# firefly.net
KiCad netlist of a schematic drawn in EAGLE
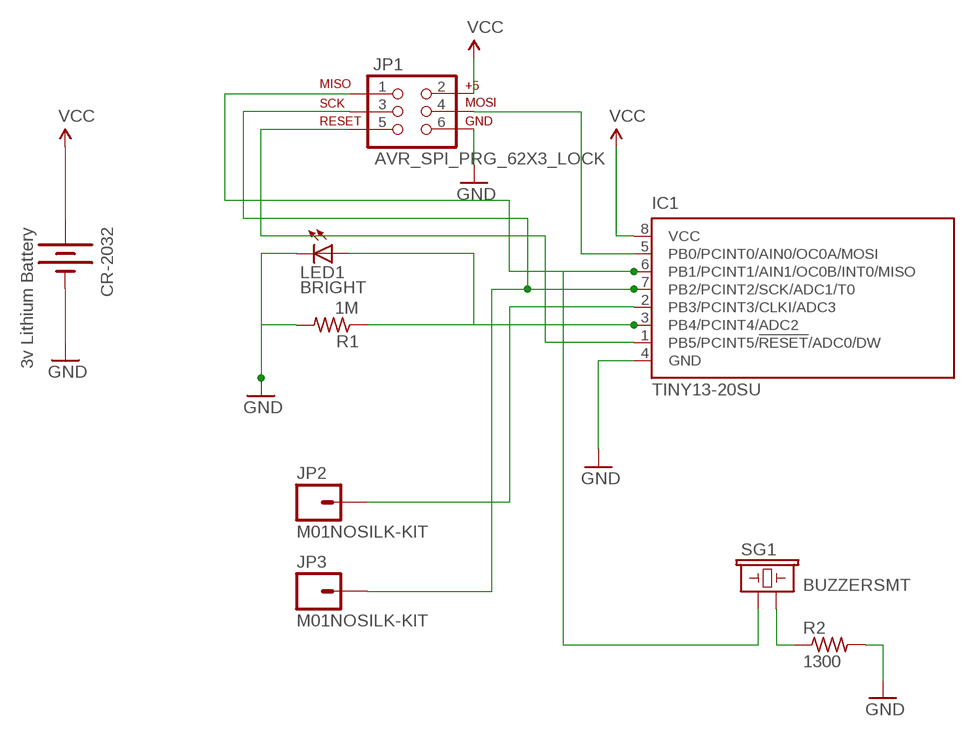
[diagram p0: schematic, sheet 1]

(export (version "E")
  (design (tool "Eeschema 10.0.6"))
  (components
    (comp (ref "CR-2032")
      (value "3v Lithium Battery")
      (footprint "eagle-import:BATTCON_20MM_4LEGS")
      (libsource (lib "eagle-import") (part "BATTERY20MM_4LEGS"))
    )
    (comp (ref "IC1")
      (value "TINY13-20SU")
      (footprint "eagle-import:8S2")
      (fields (field (name "MPN") "ATTINY13-20SU"))
      (libsource (lib "eagle-import") (part "TINY13SU-20"))
    )
    (comp (ref "JP1")
      (value "AVR_SPI_PRG_62X3_LOCK")
      (footprint "eagle-import:2X3_LOCK")
      (libsource (lib "eagle-import") (part "AVR_SPI_PRG_62X3_LOCK"))
    )
    (comp (ref "JP2")
      (value "M01NOSILK-KIT")
      (footprint "eagle-import:1X01NS-KIT")
      (libsource (lib "eagle-import") (part "M01NOSILK-KIT"))
    )
    (comp (ref "JP3")
      (value "M01NOSILK-KIT")
      (footprint "eagle-import:1X01NS-KIT")
      (libsource (lib "eagle-import") (part "M01NOSILK-KIT"))
    )
    (comp (ref "LED1")
      (value "BRIGHT")
      (footprint "eagle-import:CHIP-LED0603")
      (libsource (lib "eagle-import") (part "LEDCHIP-LED0603"))
    )
    (comp (ref "R1")
      (value "1M")
      (footprint "eagle-import:R0603")
      (libsource (lib "eagle-import") (part "R-US_R0603"))
    )
    (comp (ref "R2")
      (value "1300")
      (footprint "eagle-import:R1206")
      (libsource (lib "eagle-import") (part "R-US_R1206"))
    )
    (comp (ref "SG1")
      (value "BUZZERSMT")
      (footprint "eagle-import:BUZZER-9MM")
      (libsource (lib "eagle-import") (part "BUZZERSMT"))
    )
  )
  (nets
    (net (code "1") (name "GND") (class "Default")
      (node (ref "CR-2032") (pin "2") (pinfunction "-_2") (pintype "power_in"))
      (node (ref "IC1") (pin "4") (pinfunction "GND_4") (pintype "power_in"))
      (node (ref "JP1") (pin "6") (pinfunction "6_6") (pintype "passive"))
      (node (ref "LED1") (pin "C") (pinfunction "C_C") (pintype "passive"))
      (node (ref "R1") (pin "2") (pinfunction "2_2") (pintype "passive"))
      (node (ref "R2") (pin "2") (pinfunction "2_2") (pintype "passive"))
    )
    (net (code "2") (name "Net-(IC1-PB0{slash}PCINT0{slash}AIN0{slash}OC0A{slash}MOSI)") (class "Default")
      (node (ref "IC1") (pin "5") (pinfunction "PB0/PCINT0/AIN0/OC0A/MOSI_5") (pintype "bidirectional"))
      (node (ref "JP1") (pin "4") (pinfunction "4_4") (pintype "passive"))
    )
    (net (code "3") (name "Net-(IC1-PB1{slash}PCINT1{slash}AIN1{slash}OC0B{slash}INT0{slash}MISO)") (class "Default")
      (node (ref "IC1") (pin "6") (pinfunction "PB1/PCINT1/AIN1/OC0B/INT0/MISO_6") (pintype "bidirectional"))
      (node (ref "JP1") (pin "1") (pinfunction "1_1") (pintype "passive"))
      (node (ref "SG1") (pin "1") (pinfunction "1_1") (pintype "passive"))
    )
    (net (code "4") (name "Net-(IC1-PB2{slash}PCINT2{slash}SCK{slash}ADC1{slash}T0)") (class "Default")
      (node (ref "IC1") (pin "7") (pinfunction "PB2/PCINT2/SCK/ADC1/T0_7") (pintype "bidirectional"))
      (node (ref "JP1") (pin "3") (pinfunction "3_3") (pintype "passive"))
      (node (ref "JP3") (pin "1") (pinfunction "1_1") (pintype "passive"))
    )
    (net (code "5") (name "Net-(IC1-PB3{slash}PCINT3{slash}CLKI{slash}ADC3)") (class "Default")
      (node (ref "IC1") (pin "2") (pinfunction "PB3/PCINT3/CLKI/ADC3_2") (pintype "bidirectional"))
      (node (ref "JP2") (pin "1") (pinfunction "1_1") (pintype "passive"))
    )
    (net (code "6") (name "Net-(IC1-PB4{slash}PCINT4{slash}ADC2)") (class "Default")
      (node (ref "IC1") (pin "3") (pinfunction "PB4/PCINT4/ADC2_3") (pintype "bidirectional"))
      (node (ref "LED1") (pin "A") (pinfunction "A_A") (pintype "passive"))
      (node (ref "R1") (pin "1") (pinfunction "1_1") (pintype "passive"))
    )
    (net (code "7") (name "Net-(IC1-PB5{slash}PCINT5{slash}~{RESET}{slash}ADC0{slash}DW)") (class "Default")
      (node (ref "IC1") (pin "1") (pinfunction "PB5/PCINT5/~{RESET}/ADC0/DW_1") (pintype "bidirectional"))
      (node (ref "JP1") (pin "5") (pinfunction "5_5") (pintype "passive"))
    )
    (net (code "8") (name "Net-(R2-Pad1)") (class "Default")
      (node (ref "R2") (pin "1") (pinfunction "1_1") (pintype "passive"))
      (node (ref "SG1") (pin "2") (pinfunction "2_2") (pintype "passive"))
    )
    (net (code "9") (name "VCC") (class "Default")
      (node (ref "CR-2032") (pin "1") (pinfunction "+_1") (pintype "power_in"))
      (node (ref "IC1") (pin "8") (pinfunction "VCC_8") (pintype "power_in"))
      (node (ref "JP1") (pin "2") (pinfunction "2_2") (pintype "passive"))
    )
  )
)
